# Board.net
KiCad netlist of a schematic drawn in Altium Designer
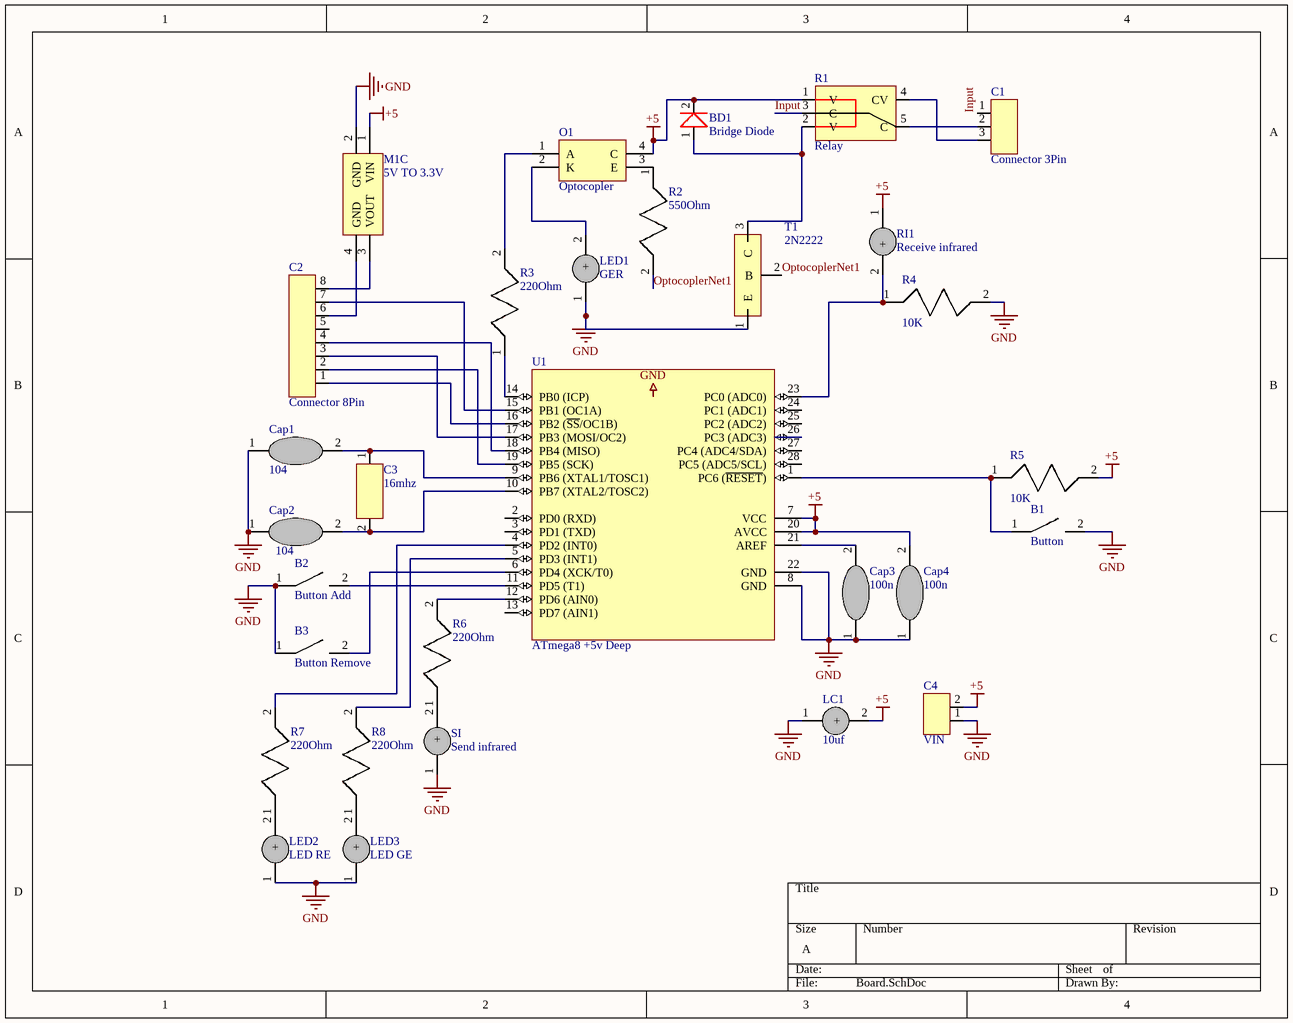
[diagram p0: Board.SchDoc]

(export (version "E")
  (design (tool "Eeschema 10.0.6"))
  (components
    (comp (ref "B1") (value "Button") (footprint "Button") (libsource (lib "Board") (part "Button")))
    (comp (ref "B2") (value "Button Add") (footprint "Button") (libsource (lib "Board") (part "Button")))
    (comp (ref "B3") (value "Button Remove") (footprint "Button") (libsource (lib "Board") (part "Button")))
    (comp (ref "BD1")
      (value "Bridge Diode")
      (footprint "Bridge Diode")
      (libsource (lib "Board") (part "Bridge Diode"))
    )
    (comp (ref "C1")
      (value "Connector 3Pin")
      (footprint "Connector 3Pin")
      (libsource (lib "Board") (part "Connector 3Pin"))
    )
    (comp (ref "C2")
      (value "Connector 8Pin")
      (footprint "Connector 8Pin")
      (libsource (lib "Board") (part "Connector 8Pin"))
    )
    (comp (ref "C3")
      (value "16mhz")
      (footprint "Crystal 16mhz")
      (libsource (lib "Board") (part "Crystal 16mhz"))
    )
    (comp (ref "C4")
      (value "VIN")
      (footprint "Connector 2Pin")
      (libsource (lib "Board") (part "Connector 2Pin"))
    )
    (comp (ref "Cap1") (value "104") (footprint "Capacitor") (libsource (lib "Board") (part "Capacitor")))
    (comp (ref "Cap2") (value "104") (footprint "Capacitor") (libsource (lib "Board") (part "Capacitor")))
    (comp (ref "Cap3") (value "100n") (footprint "Capacitor") (libsource (lib "") (part "Capacitor_1")))
    (comp (ref "Cap4") (value "100n") (footprint "Capacitor") (libsource (lib "") (part "Capacitor_1")))
    (comp (ref "LC1")
      (value "10uf")
      (footprint "Electrolytic Capacitor")
      (libsource (lib "Board") (part "Electrolytic Capacitor"))
    )
    (comp (ref "LED1") (value "GER") (footprint "LED") (libsource (lib "Board") (part "LED")))
    (comp (ref "LED2") (value "LED RE") (footprint "LED") (libsource (lib "Board") (part "LED")))
    (comp (ref "LED3") (value "LED GE") (footprint "LED") (libsource (lib "Board") (part "LED")))
    (comp (ref "M1")
      (value "5V TO 3.3V")
      (footprint "5V TO 3V")
      (libsource (lib "Board") (part "5V TO 3.3V"))
    )
    (comp (ref "O1")
      (value "Optocopler")
      (footprint "Optocopler")
      (libsource (lib "Board") (part "Optocopler"))
    )
    (comp (ref "R1") (value "Relay") (footprint "Relay") (libsource (lib "Board") (part "Relay")))
    (comp (ref "R2") (value "550Ohm") (footprint "Resistor") (libsource (lib "Board") (part "Resistor")))
    (comp (ref "R3") (value "220Ohm") (footprint "Resistor") (libsource (lib "Board") (part "Resistor")))
    (comp (ref "R4") (value "10K") (footprint "Resistor") (libsource (lib "Board") (part "Resistor")))
    (comp (ref "R5") (value "10K") (footprint "Resistor") (libsource (lib "Board") (part "Resistor")))
    (comp (ref "R6") (value "220Ohm") (footprint "Resistor") (libsource (lib "Board") (part "Resistor")))
    (comp (ref "R7") (value "220Ohm") (footprint "Resistor") (libsource (lib "Board") (part "Resistor")))
    (comp (ref "R8") (value "220Ohm") (footprint "Resistor") (libsource (lib "Board") (part "Resistor")))
    (comp (ref "RI1") (value "Receive infrared") (footprint "LED") (libsource (lib "Board") (part "LED")))
    (comp (ref "SI") (value "Send infrared") (footprint "LED") (libsource (lib "Board") (part "LED")))
    (comp (ref "T1") (value "2N2222") (footprint "Transistor") (libsource (lib "Board") (part "Transistor")))
    (comp (ref "U1")
      (value "ATmega8 +5v Deep")
      (footprint "28P3")
      (description "8-Bit AVR Microcontroller with 8K Bytes of In-System Programmable Flash Memory")
      (fields (field (name "PUBLISHER") "Altium Limited"))
      (libsource (lib "Atmel Microcontroller 8-Bit AVR") (part "ATmega8L-8PI"))
    )
  )
  (nets
    (net (code "1") (name "+5") (class "Default")
      (node (ref "BD1") (pin "2") (pintype "passive"))
      (node (ref "C4") (pin "2") (pintype "passive"))
      (node (ref "Cap4") (pin "2") (pintype "passive"))
      (node (ref "LC1") (pin "2") (pinfunction "+_2") (pintype "passive"))
      (node (ref "M1") (pin "1") (pinfunction "VIN_1") (pintype "passive"))
      (node (ref "O1") (pin "4") (pinfunction "C_4") (pintype "passive"))
      (node (ref "R1") (pin "1") (pinfunction "V_1") (pintype "passive"))
      (node (ref "R5") (pin "2") (pintype "passive"))
      (node (ref "RI1") (pin "1") (pintype "passive"))
      (node (ref "U1") (pin "20") (pinfunction "AVCC_20") (pintype "power_in"))
      (node (ref "U1") (pin "7") (pinfunction "VCC_7") (pintype "power_in"))
    )
    (net (code "2") (name "/Input") (class "Default")
      (node (ref "C1") (pin "1") (pintype "passive"))
      (node (ref "R1") (pin "3") (pinfunction "C_3") (pintype "passive"))
    )
    (net (code "3") (name "/OptocoplerNet1") (class "Default")
      (node (ref "R2") (pin "2") (pintype "passive"))
      (node (ref "T1") (pin "2") (pinfunction "B_2") (pintype "passive"))
    )
    (net (code "4") (name "GND") (class "Default")
      (node (ref "B1") (pin "2") (pintype "passive"))
      (node (ref "B2") (pin "1") (pintype "passive"))
      (node (ref "B3") (pin "1") (pintype "passive"))
      (node (ref "C4") (pin "1") (pintype "passive"))
      (node (ref "Cap1") (pin "1") (pintype "passive"))
      (node (ref "Cap2") (pin "1") (pintype "passive"))
      (node (ref "Cap3") (pin "1") (pintype "passive"))
      (node (ref "Cap4") (pin "1") (pintype "passive"))
      (node (ref "LC1") (pin "1") (pintype "passive"))
      (node (ref "LED1") (pin "1") (pintype "passive"))
      (node (ref "LED2") (pin "1") (pintype "passive"))
      (node (ref "LED3") (pin "1") (pintype "passive"))
      (node (ref "M1") (pin "2") (pinfunction "GND_2") (pintype "passive"))
      (node (ref "R4") (pin "2") (pintype "passive"))
      (node (ref "SI") (pin "1") (pintype "passive"))
      (node (ref "T1") (pin "1") (pinfunction "E_1") (pintype "passive"))
      (node (ref "U1") (pin "22") (pinfunction "GND_22") (pintype "power_in"))
      (node (ref "U1") (pin "8") (pinfunction "GND_8") (pintype "power_in"))
    )
    (net (code "5") (name "Net-(C1-Pad2)") (class "Default")
      (node (ref "C1") (pin "2") (pintype "passive"))
      (node (ref "R1") (pin "5") (pinfunction "C_5") (pintype "passive"))
    )
    (net (code "6") (name "Net-(C2-Pad6)") (class "Default")
      (node (ref "C2") (pin "6") (pintype "passive"))
      (node (ref "M1") (pin "4") (pinfunction "GND_4") (pintype "passive"))
    )
    (net (code "7") (name "Net-(LED1-+)") (class "Default")
      (node (ref "LED1") (pin "2") (pinfunction "+_2") (pintype "passive"))
      (node (ref "O1") (pin "2") (pinfunction "K_2") (pintype "passive"))
    )
    (net (code "8") (name "Net-(LED2-+)") (class "Default")
      (node (ref "LED2") (pin "2") (pinfunction "+_2") (pintype "passive"))
      (node (ref "R7") (pin "1") (pintype "passive"))
    )
    (net (code "9") (name "Net-(LED3-+)") (class "Default")
      (node (ref "LED3") (pin "2") (pinfunction "+_2") (pintype "passive"))
      (node (ref "R8") (pin "1") (pintype "passive"))
    )
    (net (code "10") (name "Net-(M1C-VOUT)") (class "Default")
      (node (ref "C2") (pin "8") (pintype "passive"))
      (node (ref "M1") (pin "3") (pinfunction "VOUT_3") (pintype "passive"))
    )
    (net (code "11") (name "Net-(O1-A)") (class "Default")
      (node (ref "O1") (pin "1") (pinfunction "A_1") (pintype "passive"))
      (node (ref "R3") (pin "2") (pintype "passive"))
    )
    (net (code "12") (name "Net-(O1-E)") (class "Default")
      (node (ref "O1") (pin "3") (pinfunction "E_3") (pintype "passive"))
      (node (ref "R2") (pin "1") (pintype "passive"))
    )
    (net (code "13") (name "Net-(R1-CV)") (class "Default")
      (node (ref "C1") (pin "3") (pintype "passive"))
      (node (ref "R1") (pin "4") (pinfunction "CV_4") (pintype "passive"))
    )
    (net (code "14") (name "Net-(RI1-+)") (class "Default")
      (node (ref "R4") (pin "1") (pintype "passive"))
      (node (ref "RI1") (pin "2") (pinfunction "+_2") (pintype "passive"))
      (node (ref "U1") (pin "23") (pinfunction "PC0_(ADC0)_23") (pintype "bidirectional"))
    )
    (net (code "15") (name "Net-(SI-+)") (class "Default")
      (node (ref "R6") (pin "1") (pintype "passive"))
      (node (ref "SI") (pin "2") (pinfunction "+_2") (pintype "passive"))
    )
    (net (code "16") (name "Net-(T1-C)") (class "Default")
      (node (ref "BD1") (pin "1") (pintype "passive"))
      (node (ref "R1") (pin "2") (pinfunction "V_2") (pintype "passive"))
      (node (ref "T1") (pin "3") (pinfunction "C_3") (pintype "passive"))
    )
    (net (code "17") (name "Net-(U1-AREF)") (class "Default")
      (node (ref "Cap3") (pin "2") (pintype "passive"))
      (node (ref "U1") (pin "21") (pinfunction "AREF_21") (pintype "passive"))
    )
    (net (code "18") (name "Net-(U1-PB0_(ICP))") (class "Default")
      (node (ref "R3") (pin "1") (pintype "passive"))
      (node (ref "U1") (pin "14") (pinfunction "PB0_(ICP)_14") (pintype "bidirectional"))
    )
    (net (code "19") (name "Net-(U1-PB1_(OC1A))") (class "Default")
      (node (ref "C2") (pin "7") (pintype "passive"))
      (node (ref "U1") (pin "15") (pinfunction "PB1_(OC1A)_15") (pintype "bidirectional"))
    )
    (net (code "20") (name "Net-(U1-PB2_(~{SS}{slash}OC1B))") (class "Default")
      (node (ref "C2") (pin "1") (pintype "passive"))
      (node (ref "U1") (pin "16") (pinfunction "PB2_(~{SS}/OC1B)_16") (pintype "bidirectional"))
    )
    (net (code "21") (name "Net-(U1-PB3_(MOSI{slash}OC2))") (class "Default")
      (node (ref "C2") (pin "3") (pintype "passive"))
      (node (ref "U1") (pin "17") (pinfunction "PB3_(MOSI/OC2)_17") (pintype "bidirectional"))
    )
    (net (code "22") (name "Net-(U1-PB4_(MISO))") (class "Default")
      (node (ref "C2") (pin "4") (pintype "passive"))
      (node (ref "U1") (pin "18") (pinfunction "PB4_(MISO)_18") (pintype "bidirectional"))
    )
    (net (code "23") (name "Net-(U1-PB5_(SCK))") (class "Default")
      (node (ref "C2") (pin "2") (pintype "passive"))
      (node (ref "U1") (pin "19") (pinfunction "PB5_(SCK)_19") (pintype "bidirectional"))
    )
    (net (code "24") (name "Net-(U1-PB6_(XTAL1{slash}TOSC1))") (class "Default")
      (node (ref "C3") (pin "1") (pintype "passive"))
      (node (ref "Cap1") (pin "2") (pintype "passive"))
      (node (ref "U1") (pin "9") (pinfunction "PB6_(XTAL1/TOSC1)_9") (pintype "bidirectional"))
    )
    (net (code "25") (name "Net-(U1-PB7_(XTAL2{slash}TOSC2))") (class "Default")
      (node (ref "C3") (pin "2") (pintype "passive"))
      (node (ref "Cap2") (pin "2") (pintype "passive"))
      (node (ref "U1") (pin "10") (pinfunction "PB7_(XTAL2/TOSC2)_10") (pintype "bidirectional"))
    )
    (net (code "26") (name "Net-(U1-PC6_(~{RESET}))") (class "Default")
      (node (ref "B1") (pin "1") (pintype "passive"))
      (node (ref "R5") (pin "1") (pintype "passive"))
      (node (ref "U1") (pin "1") (pinfunction "PC6_(~{RESET})_1") (pintype "bidirectional"))
    )
    (net (code "27") (name "Net-(U1-PD2_(INT0))") (class "Default")
      (node (ref "R7") (pin "2") (pintype "passive"))
      (node (ref "U1") (pin "4") (pinfunction "PD2_(INT0)_4") (pintype "bidirectional"))
    )
    (net (code "28") (name "Net-(U1-PD3_(INT1))") (class "Default")
      (node (ref "R8") (pin "2") (pintype "passive"))
      (node (ref "U1") (pin "5") (pinfunction "PD3_(INT1)_5") (pintype "bidirectional"))
    )
    (net (code "29") (name "Net-(U1-PD4_(XCK{slash}T0))") (class "Default")
      (node (ref "B3") (pin "2") (pintype "passive"))
      (node (ref "U1") (pin "6") (pinfunction "PD4_(XCK/T0)_6") (pintype "bidirectional"))
    )
    (net (code "30") (name "Net-(U1-PD5_(T1))") (class "Default")
      (node (ref "B2") (pin "2") (pintype "passive"))
      (node (ref "U1") (pin "11") (pinfunction "PD5_(T1)_11") (pintype "bidirectional"))
    )
    (net (code "31") (name "Net-(U1-PD6_(AIN0))") (class "Default")
      (node (ref "R6") (pin "2") (pintype "passive"))
      (node (ref "U1") (pin "12") (pinfunction "PD6_(AIN0)_12") (pintype "bidirectional"))
    )
    (net (code "32") (name "unconnected-(C2-Pad5)") (class "Default")
      (node (ref "C2") (pin "5") (pintype "passive"))
    )
    (net (code "33") (name "unconnected-(U1-PC1_(ADC1)-Pad24)") (class "Default")
      (node (ref "U1") (pin "24") (pinfunction "PC1_(ADC1)_24") (pintype "bidirectional"))
    )
    (net (code "34") (name "unconnected-(U1-PC2_(ADC2)-Pad25)") (class "Default")
      (node (ref "U1") (pin "25") (pinfunction "PC2_(ADC2)_25") (pintype "bidirectional"))
    )
    (net (code "35") (name "unconnected-(U1-PC3_(ADC3)-Pad26)") (class "Default")
      (node (ref "U1") (pin "26") (pinfunction "PC3_(ADC3)_26") (pintype "bidirectional"))
    )
    (net (code "36") (name "unconnected-(U1-PC4_(ADC4{slash}SDA)-Pad27)") (class "Default")
      (node (ref "U1") (pin "27") (pinfunction "PC4_(ADC4/SDA)_27") (pintype "bidirectional"))
    )
    (net (code "37") (name "unconnected-(U1-PC5_(ADC5{slash}SCL)-Pad28)") (class "Default")
      (node (ref "U1") (pin "28") (pinfunction "PC5_(ADC5/SCL)_28") (pintype "bidirectional"))
    )
    (net (code "38") (name "unconnected-(U1-PD0_(RXD)-Pad2)") (class "Default")
      (node (ref "U1") (pin "2") (pinfunction "PD0_(RXD)_2") (pintype "bidirectional"))
    )
    (net (code "39") (name "unconnected-(U1-PD1_(TXD)-Pad3)") (class "Default")
      (node (ref "U1") (pin "3") (pinfunction "PD1_(TXD)_3") (pintype "bidirectional"))
    )
    (net (code "40") (name "unconnected-(U1-PD7_(AIN1)-Pad13)") (class "Default")
      (node (ref "U1") (pin "13") (pinfunction "PD7_(AIN1)_13") (pintype "bidirectional"))
    )
  )
)
